# SCH_mini_attiny_2026-08-26.net
KiCad netlist of a schematic drawn in EasyEDA
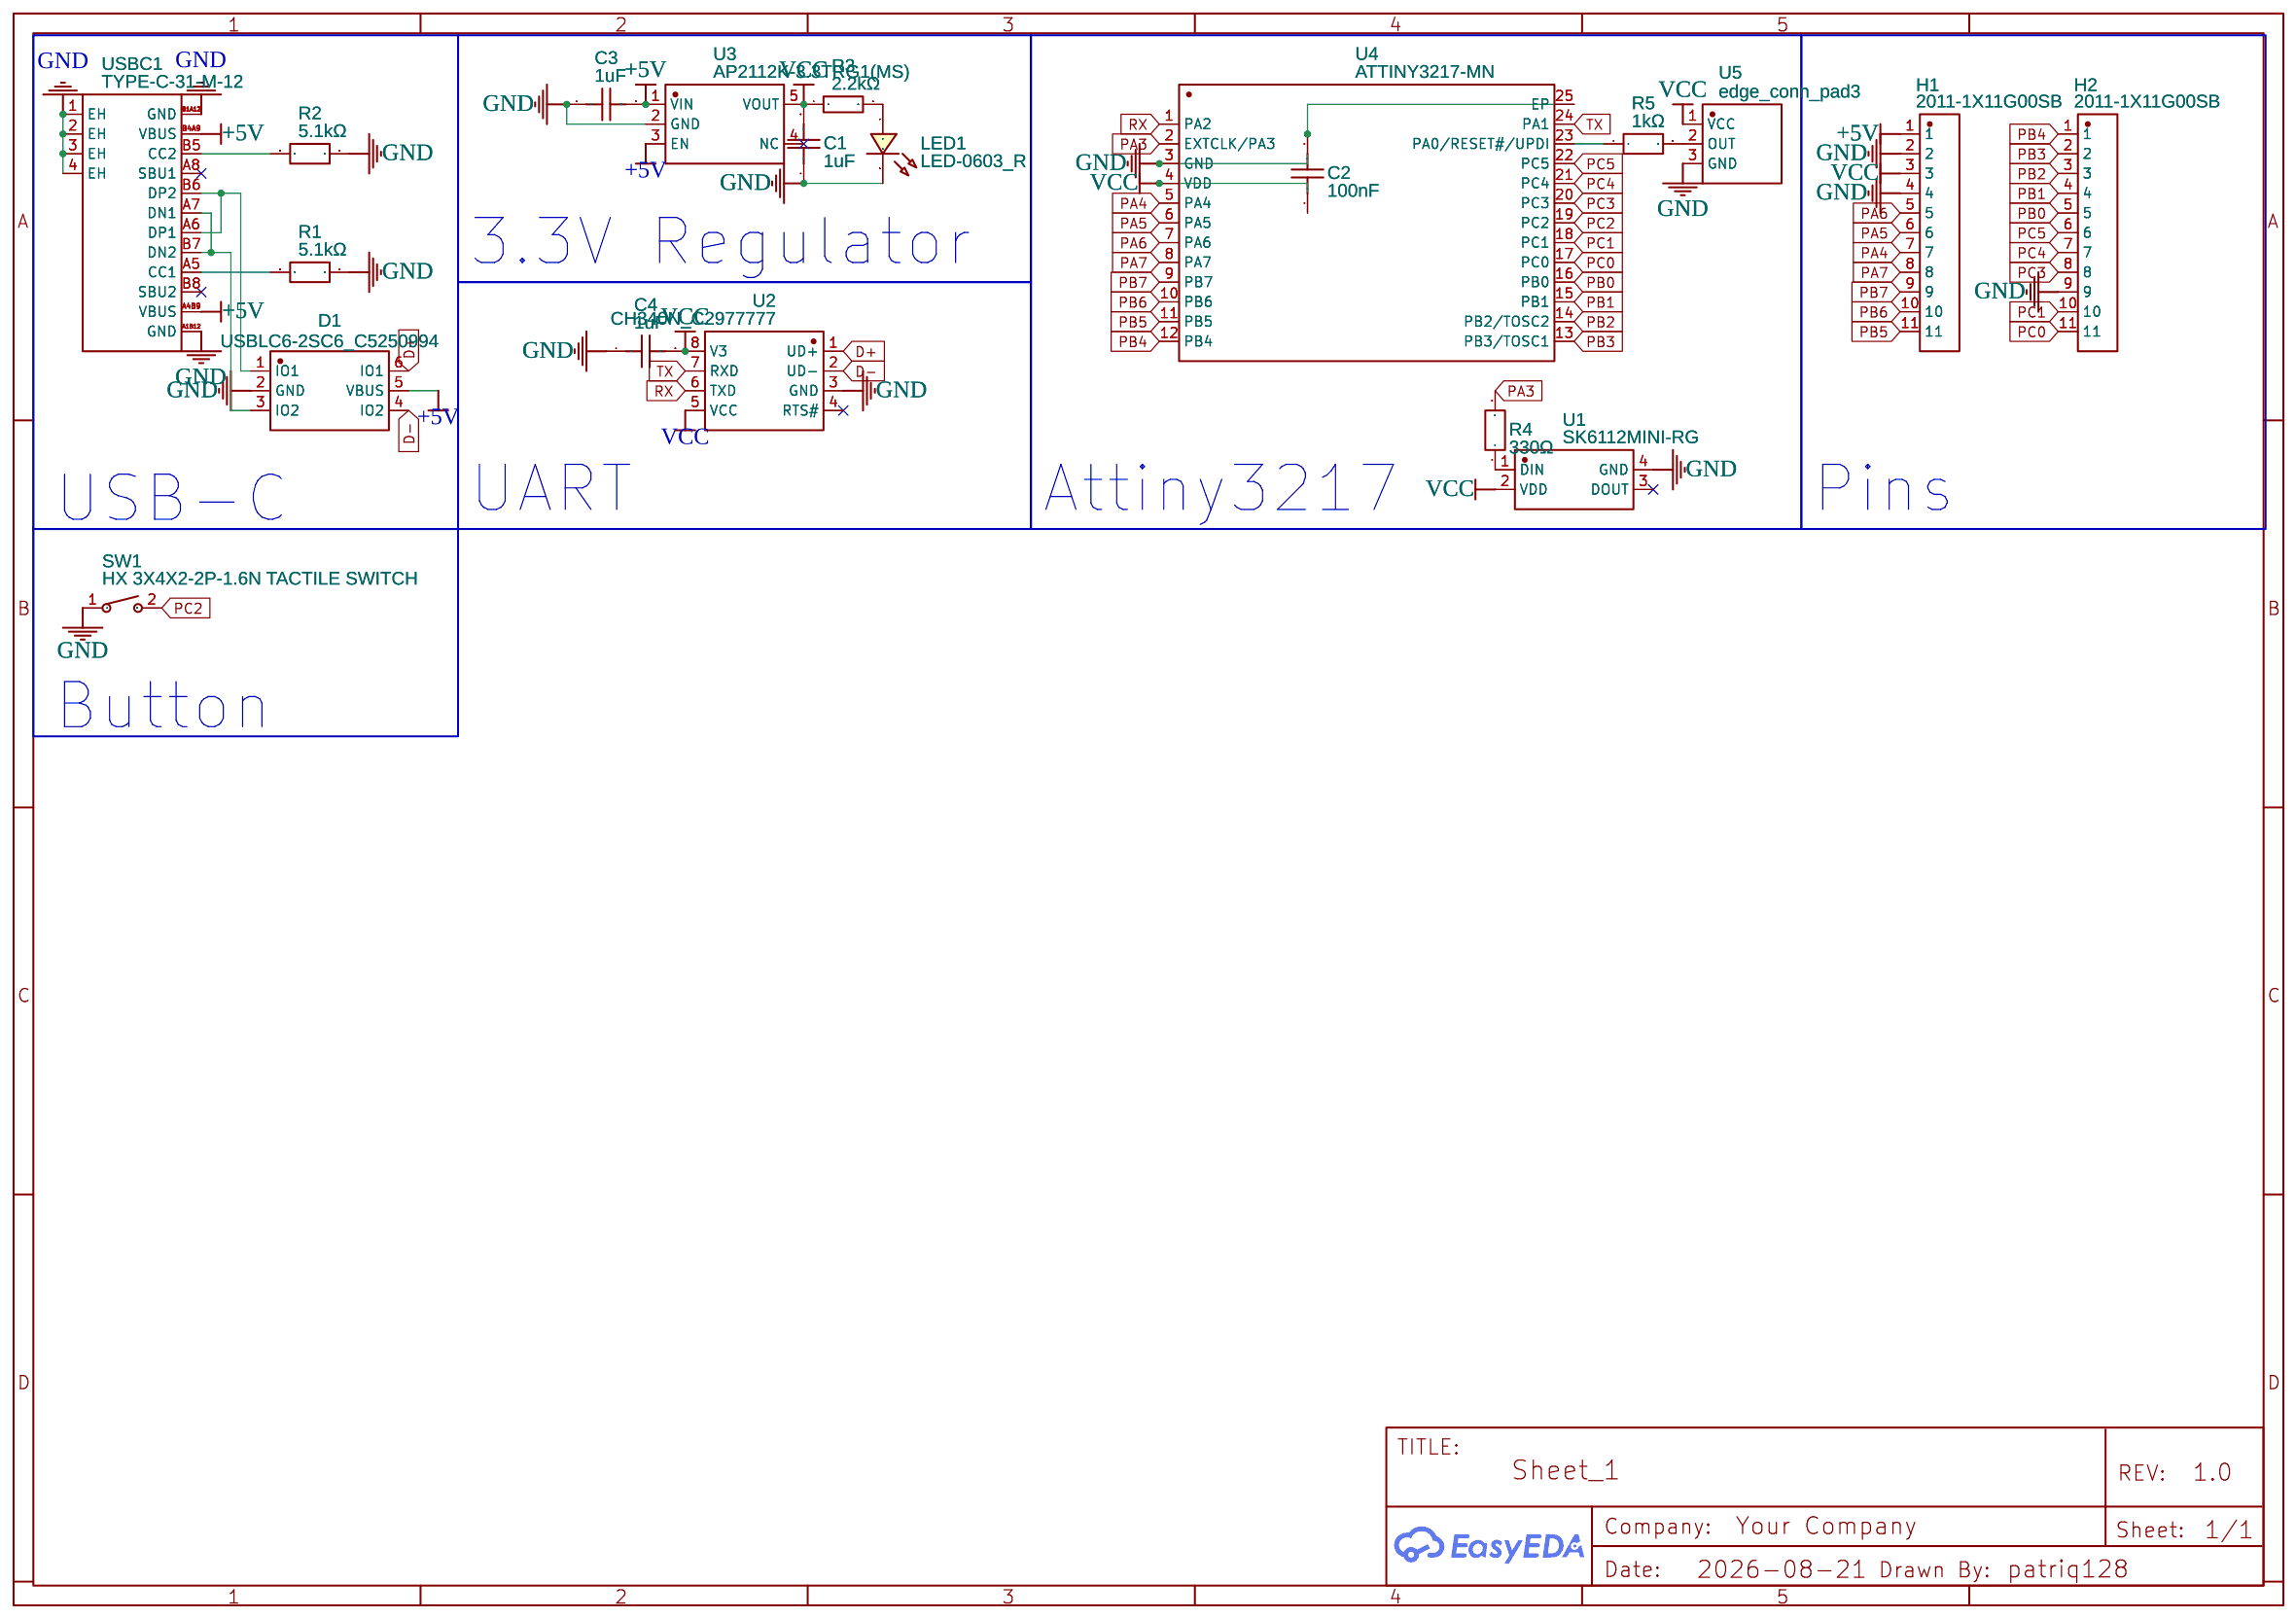
[diagram p0: schematic sheet]

(export (version "E")
  (design (tool "Eeschema 10.0.6"))
  (components
    (comp (ref "C1")
      (value "1uF")
      (fields (field (name "Manufacturer Part") "06033D105MAT2A") (field (name "Manufacturer") "Kyocera AVX"))
      (libsource (lib "") (part "06033D105MAT2A_1"))
    )
    (comp (ref "C2")
      (value "100nF")
      (fields (field (name "Manufacturer Part") "06033C104K4T2A") (field (name "Manufacturer") "Kyocera AVX"))
      (libsource (lib "") (part "06033C104K4T2A"))
    )
    (comp (ref "C3")
      (value "1uF")
      (fields (field (name "Manufacturer Part") "06033D105MAT2A") (field (name "Manufacturer") "Kyocera AVX"))
      (libsource (lib "") (part "06033D105MAT2A"))
    )
    (comp (ref "C4")
      (value "1uF")
      (fields (field (name "Manufacturer Part") "06033D105MAT2A") (field (name "Manufacturer") "Kyocera AVX"))
      (libsource (lib "") (part "06033D105MAT2A"))
    )
    (comp (ref "D1")
      (value "USBLC6-2SC6_C5250994")
      (fields (field (name "Manufacturer Part") "USBLC6-2SC6") (field (name "Manufacturer") "TWGMC(迪嘉)"))
      (libsource (lib "") (part "USBLC6-2SC6_C5250994"))
    )
    (comp (ref "H1")
      (value "2011-1X11G00SB")
      (fields (field (name "Manufacturer") "WingTAT(格林柏)"))
      (libsource (lib "") (part "2011-1X11G00SB"))
    )
    (comp (ref "H2")
      (value "2011-1X11G00SB")
      (fields (field (name "Manufacturer") "WingTAT(格林柏)"))
      (libsource (lib "") (part "2011-1X11G00SB"))
    )
    (comp (ref "LED1")
      (value "LED-0603_R")
      (fields
        (field (name "Manufacturer Part") "19-217/R6C-AL1M2VY/3T")
        (field (name "Manufacturer") "EVERLIGHT(台湾亿光)")
      )
      (libsource (lib "") (part "LED-0603_R"))
    )
    (comp (ref "R1")
      (value "5.1kΩ")
      (fields
        (field (name "Manufacturer Part") "HoAR0603-1/10W-5.1KR-0.1%-TCR25")
        (field (name "Manufacturer") "Milliohm(毫欧)")
      )
      (libsource (lib "") (part "HOAR0603-1/10W-5.1KR-0.1%-TCR25"))
    )
    (comp (ref "R2")
      (value "5.1kΩ")
      (fields
        (field (name "Manufacturer Part") "HoAR0603-1/10W-5.1KR-0.1%-TCR25")
        (field (name "Manufacturer") "Milliohm(毫欧)")
      )
      (libsource (lib "") (part "HOAR0603-1/10W-5.1KR-0.1%-TCR25"))
    )
    (comp (ref "R3")
      (value "2.2kΩ")
      (fields (field (name "Manufacturer Part") "RMC06032.2K1%N") (field (name "Manufacturer") "Tyohm(幸亚电阻)"))
      (libsource (lib "") (part "RMC06032.2K1%N"))
    )
    (comp (ref "R4")
      (value "330Ω")
      (fields
        (field (name "Manufacturer Part") "0603WAD3300T5E")
        (field (name "Manufacturer") "UNI-ROYAL(厚声)")
      )
      (libsource (lib "") (part "0603WAD3300T5E"))
    )
    (comp (ref "R5")
      (value "1kΩ")
      (fields
        (field (name "Manufacturer Part") "RMC 0603 1K J N")
        (field (name "Manufacturer") "Tyohm(幸亚电阻)")
      )
      (libsource (lib "") (part "RMC 0603 1K J N"))
    )
    (comp (ref "SW1")
      (value "HX 3X4X2-2P-1.6N TACTILE SWITCH")
      (fields
        (field (name "Manufacturer Part") "HX 3x4x2-2P-1.6N TACTILE SWITCH")
        (field (name "Manufacturer") "hanxia(韩下)")
      )
      (libsource (lib "") (part "HX 3X4X2-2P-1.6N TACTILE SWITCH"))
    )
    (comp (ref "U1")
      (value "SK6112MINI-RG")
      (fields (field (name "Manufacturer") "欧思科光电"))
      (libsource (lib "") (part "SK6112MINI-RG"))
    )
    (comp (ref "U2")
      (value "CH340N_C2977777")
      (fields (field (name "Manufacturer Part") "CH340N") (field (name "Manufacturer") "WCH(南京沁恒)"))
      (libsource (lib "") (part "CH340N_C2977777"))
    )
    (comp (ref "U3")
      (value "AP2112K-3.3TRG1(MS)")
      (fields (field (name "Manufacturer") "MSKSEMI(美森科)"))
      (libsource (lib "") (part "AP2112K-3.3TRG1(MS)"))
    )
    (comp (ref "U4")
      (value "ATTINY3217-MN")
      (fields (field (name "Manufacturer") "MICROCHIP(美国微芯)"))
      (libsource (lib "") (part "ATTINY3217-MN"))
    )
    (comp (ref "U5") (value "edge_conn_pad3") (libsource (lib "") (part "edge_conn_pad3")))
    (comp (ref "USBC1")
      (value "TYPE-C-31-M-12")
      (fields (field (name "Manufacturer") "韩国韩荣"))
      (libsource (lib "") (part "TYPE-C-31-M-12"))
    )
  )
  (nets
    (net (code "1") (name "+5V") (class "Default")
      (node (ref "C3") (pin "2") (pinfunction "2_2") (pintype "unspecified"))
      (node (ref "D1") (pin "5") (pinfunction "VBUS_5") (pintype "unspecified"))
      (node (ref "H1") (pin "1") (pinfunction "1_1") (pintype "unspecified"))
      (node (ref "U3") (pin "1") (pinfunction "VIN_1") (pintype "unspecified"))
      (node (ref "U3") (pin "3") (pinfunction "EN_3") (pintype "unspecified"))
      (node (ref "USBC1") (pin "A4B9") (pinfunction "VBUS_A4B9") (pintype "unspecified"))
      (node (ref "USBC1") (pin "B4A9") (pinfunction "VBUS_B4A9") (pintype "unspecified"))
    )
    (net (code "2") (name "D+") (class "Default")
      (node (ref "D1") (pin "6") (pinfunction "IO1_6") (pintype "unspecified"))
      (node (ref "U2") (pin "1") (pinfunction "UD+_1") (pintype "unspecified"))
    )
    (net (code "3") (name "D-") (class "Default")
      (node (ref "D1") (pin "4") (pinfunction "IO2_4") (pintype "unspecified"))
      (node (ref "U2") (pin "2") (pinfunction "UD-_2") (pintype "unspecified"))
    )
    (net (code "4") (name "GND") (class "Default")
      (node (ref "C1") (pin "1") (pinfunction "1_1") (pintype "unspecified"))
      (node (ref "C2") (pin "2") (pinfunction "2_2") (pintype "unspecified"))
      (node (ref "C3") (pin "1") (pinfunction "1_1") (pintype "unspecified"))
      (node (ref "C4") (pin "1") (pinfunction "1_1") (pintype "unspecified"))
      (node (ref "D1") (pin "2") (pinfunction "GND_2") (pintype "unspecified"))
      (node (ref "H1") (pin "2") (pinfunction "2_2") (pintype "unspecified"))
      (node (ref "H1") (pin "4") (pinfunction "4_4") (pintype "unspecified"))
      (node (ref "H2") (pin "9") (pinfunction "9_9") (pintype "unspecified"))
      (node (ref "LED1") (pin "2") (pinfunction "2_2") (pintype "unspecified"))
      (node (ref "R1") (pin "1") (pinfunction "1_1") (pintype "unspecified"))
      (node (ref "R2") (pin "1") (pinfunction "1_1") (pintype "unspecified"))
      (node (ref "SW1") (pin "1") (pinfunction "1_1") (pintype "unspecified"))
      (node (ref "U1") (pin "4") (pinfunction "GND_4") (pintype "unspecified"))
      (node (ref "U2") (pin "3") (pinfunction "GND_3") (pintype "unspecified"))
      (node (ref "U3") (pin "2") (pinfunction "GND_2") (pintype "unspecified"))
      (node (ref "U4") (pin "25") (pinfunction "EP_25") (pintype "unspecified"))
      (node (ref "U4") (pin "3") (pinfunction "GND_3") (pintype "unspecified"))
      (node (ref "U5") (pin "3") (pinfunction "GND_3") (pintype "unspecified"))
      (node (ref "USBC1") (pin "1") (pinfunction "EH_1") (pintype "unspecified"))
      (node (ref "USBC1") (pin "2") (pinfunction "EH_2") (pintype "unspecified"))
      (node (ref "USBC1") (pin "3") (pinfunction "EH_3") (pintype "unspecified"))
      (node (ref "USBC1") (pin "4") (pinfunction "EH_4") (pintype "unspecified"))
      (node (ref "USBC1") (pin "A1B12") (pinfunction "GND_A1B12") (pintype "unspecified"))
      (node (ref "USBC1") (pin "B1A12") (pinfunction "GND_B1A12") (pintype "unspecified"))
    )
    (net (code "5") (name "Net-(LED1-Pad1)") (class "Default")
      (node (ref "LED1") (pin "1") (pinfunction "1_1") (pintype "unspecified"))
      (node (ref "R3") (pin "2") (pinfunction "2_2") (pintype "unspecified"))
    )
    (net (code "6") (name "Net-(U1-DIN)") (class "Default")
      (node (ref "R4") (pin "1") (pinfunction "1_1") (pintype "unspecified"))
      (node (ref "U1") (pin "1") (pinfunction "DIN_1") (pintype "unspecified"))
    )
    (net (code "7") (name "Net-(U4-PA0{slash}RESET#{slash}UPDI)") (class "Default")
      (node (ref "R5") (pin "1") (pinfunction "1_1") (pintype "unspecified"))
      (node (ref "U4") (pin "23") (pinfunction "PA0/RESET#/UPDI_23") (pintype "unspecified"))
    )
    (net (code "8") (name "Net-(U5-OUT)") (class "Default")
      (node (ref "R5") (pin "2") (pinfunction "2_2") (pintype "unspecified"))
      (node (ref "U5") (pin "2") (pinfunction "OUT_2") (pintype "unspecified"))
    )
    (net (code "9") (name "Net-(USBC1-CC1)") (class "Default")
      (node (ref "R1") (pin "2") (pinfunction "2_2") (pintype "unspecified"))
      (node (ref "USBC1") (pin "A5") (pinfunction "CC1_A5") (pintype "unspecified"))
    )
    (net (code "10") (name "Net-(USBC1-CC2)") (class "Default")
      (node (ref "R2") (pin "2") (pinfunction "2_2") (pintype "unspecified"))
      (node (ref "USBC1") (pin "B5") (pinfunction "CC2_B5") (pintype "unspecified"))
    )
    (net (code "11") (name "Net-(USBC1-DN1)") (class "Default")
      (node (ref "D1") (pin "3") (pinfunction "IO2_3") (pintype "unspecified"))
      (node (ref "USBC1") (pin "A7") (pinfunction "DN1_A7") (pintype "unspecified"))
      (node (ref "USBC1") (pin "B7") (pinfunction "DN2_B7") (pintype "unspecified"))
    )
    (net (code "12") (name "Net-(USBC1-DP1)") (class "Default")
      (node (ref "D1") (pin "1") (pinfunction "IO1_1") (pintype "unspecified"))
      (node (ref "USBC1") (pin "A6") (pinfunction "DP1_A6") (pintype "unspecified"))
      (node (ref "USBC1") (pin "B6") (pinfunction "DP2_B6") (pintype "unspecified"))
    )
    (net (code "13") (name "PA3") (class "Default")
      (node (ref "R4") (pin "2") (pinfunction "2_2") (pintype "unspecified"))
      (node (ref "U4") (pin "2") (pinfunction "EXTCLK/PA3_2") (pintype "unspecified"))
    )
    (net (code "14") (name "PA4") (class "Default")
      (node (ref "H1") (pin "7") (pinfunction "7_7") (pintype "unspecified"))
      (node (ref "U4") (pin "5") (pinfunction "PA4_5") (pintype "unspecified"))
    )
    (net (code "15") (name "PA5") (class "Default")
      (node (ref "H1") (pin "6") (pinfunction "6_6") (pintype "unspecified"))
      (node (ref "U4") (pin "6") (pinfunction "PA5_6") (pintype "unspecified"))
    )
    (net (code "16") (name "PA6") (class "Default")
      (node (ref "H1") (pin "5") (pinfunction "5_5") (pintype "unspecified"))
      (node (ref "U4") (pin "7") (pinfunction "PA6_7") (pintype "unspecified"))
    )
    (net (code "17") (name "PA7") (class "Default")
      (node (ref "H1") (pin "8") (pinfunction "8_8") (pintype "unspecified"))
      (node (ref "U4") (pin "8") (pinfunction "PA7_8") (pintype "unspecified"))
    )
    (net (code "18") (name "PB0") (class "Default")
      (node (ref "H2") (pin "5") (pinfunction "5_5") (pintype "unspecified"))
      (node (ref "U4") (pin "16") (pinfunction "PB0_16") (pintype "unspecified"))
    )
    (net (code "19") (name "PB1") (class "Default")
      (node (ref "H2") (pin "4") (pinfunction "4_4") (pintype "unspecified"))
      (node (ref "U4") (pin "15") (pinfunction "PB1_15") (pintype "unspecified"))
    )
    (net (code "20") (name "PB2") (class "Default")
      (node (ref "H2") (pin "3") (pinfunction "3_3") (pintype "unspecified"))
      (node (ref "U4") (pin "14") (pinfunction "PB2/TOSC2_14") (pintype "unspecified"))
    )
    (net (code "21") (name "PB3") (class "Default")
      (node (ref "H2") (pin "2") (pinfunction "2_2") (pintype "unspecified"))
      (node (ref "U4") (pin "13") (pinfunction "PB3/TOSC1_13") (pintype "unspecified"))
    )
    (net (code "22") (name "PB4") (class "Default")
      (node (ref "H2") (pin "1") (pinfunction "1_1") (pintype "unspecified"))
      (node (ref "U4") (pin "12") (pinfunction "PB4_12") (pintype "unspecified"))
    )
    (net (code "23") (name "PB5") (class "Default")
      (node (ref "H1") (pin "11") (pinfunction "11_11") (pintype "unspecified"))
      (node (ref "U4") (pin "11") (pinfunction "PB5_11") (pintype "unspecified"))
    )
    (net (code "24") (name "PB6") (class "Default")
      (node (ref "H1") (pin "10") (pinfunction "10_10") (pintype "unspecified"))
      (node (ref "U4") (pin "10") (pinfunction "PB6_10") (pintype "unspecified"))
    )
    (net (code "25") (name "PB7") (class "Default")
      (node (ref "H1") (pin "9") (pinfunction "9_9") (pintype "unspecified"))
      (node (ref "U4") (pin "9") (pinfunction "PB7_9") (pintype "unspecified"))
    )
    (net (code "26") (name "PC0") (class "Default")
      (node (ref "H2") (pin "11") (pinfunction "11_11") (pintype "unspecified"))
      (node (ref "U4") (pin "17") (pinfunction "PC0_17") (pintype "unspecified"))
    )
    (net (code "27") (name "PC1") (class "Default")
      (node (ref "H2") (pin "10") (pinfunction "10_10") (pintype "unspecified"))
      (node (ref "U4") (pin "18") (pinfunction "PC1_18") (pintype "unspecified"))
    )
    (net (code "28") (name "PC2") (class "Default")
      (node (ref "SW1") (pin "2") (pinfunction "2_2") (pintype "unspecified"))
      (node (ref "U4") (pin "19") (pinfunction "PC2_19") (pintype "unspecified"))
    )
    (net (code "29") (name "PC3") (class "Default")
      (node (ref "H2") (pin "8") (pinfunction "8_8") (pintype "unspecified"))
      (node (ref "U4") (pin "20") (pinfunction "PC3_20") (pintype "unspecified"))
    )
    (net (code "30") (name "PC4") (class "Default")
      (node (ref "H2") (pin "7") (pinfunction "7_7") (pintype "unspecified"))
      (node (ref "U4") (pin "21") (pinfunction "PC4_21") (pintype "unspecified"))
    )
    (net (code "31") (name "PC5") (class "Default")
      (node (ref "H2") (pin "6") (pinfunction "6_6") (pintype "unspecified"))
      (node (ref "U4") (pin "22") (pinfunction "PC5_22") (pintype "unspecified"))
    )
    (net (code "32") (name "RX") (class "Default")
      (node (ref "U2") (pin "6") (pinfunction "TXD_6") (pintype "unspecified"))
      (node (ref "U4") (pin "1") (pinfunction "PA2_1") (pintype "unspecified"))
    )
    (net (code "33") (name "TX") (class "Default")
      (node (ref "U2") (pin "7") (pinfunction "RXD_7") (pintype "unspecified"))
      (node (ref "U4") (pin "24") (pinfunction "PA1_24") (pintype "unspecified"))
    )
    (net (code "34") (name "VCC") (class "Default")
      (node (ref "C1") (pin "2") (pinfunction "2_2") (pintype "unspecified"))
      (node (ref "C2") (pin "1") (pinfunction "1_1") (pintype "unspecified"))
      (node (ref "C4") (pin "2") (pinfunction "2_2") (pintype "unspecified"))
      (node (ref "H1") (pin "3") (pinfunction "3_3") (pintype "unspecified"))
      (node (ref "R3") (pin "1") (pinfunction "1_1") (pintype "unspecified"))
      (node (ref "U1") (pin "2") (pinfunction "VDD_2") (pintype "unspecified"))
      (node (ref "U2") (pin "5") (pinfunction "VCC_5") (pintype "unspecified"))
      (node (ref "U2") (pin "8") (pinfunction "V3_8") (pintype "unspecified"))
      (node (ref "U3") (pin "5") (pinfunction "VOUT_5") (pintype "unspecified"))
      (node (ref "U4") (pin "4") (pinfunction "VDD_4") (pintype "unspecified"))
      (node (ref "U5") (pin "1") (pinfunction "VCC_1") (pintype "unspecified"))
    )
    (net (code "35") (name "unconnected-(U1-DOUT-Pad3)") (class "Default")
      (node (ref "U1") (pin "3") (pinfunction "DOUT_3") (pintype "unspecified+no_connect"))
    )
    (net (code "36") (name "unconnected-(U2-RTS#-Pad4)") (class "Default")
      (node (ref "U2") (pin "4") (pinfunction "RTS#_4") (pintype "unspecified+no_connect"))
    )
    (net (code "37") (name "unconnected-(U3-NC-Pad4)") (class "Default")
      (node (ref "U3") (pin "4") (pinfunction "NC_4") (pintype "unspecified+no_connect"))
    )
    (net (code "38") (name "unconnected-(USBC1-SBU1-PadA8)") (class "Default")
      (node (ref "USBC1") (pin "A8") (pinfunction "SBU1_A8") (pintype "unspecified+no_connect"))
    )
    (net (code "39") (name "unconnected-(USBC1-SBU2-PadB8)") (class "Default")
      (node (ref "USBC1") (pin "B8") (pinfunction "SBU2_B8") (pintype "unspecified+no_connect"))
    )
  )
)
